# DS18B20.net
KiCad netlist of a schematic drawn in Altium Designer
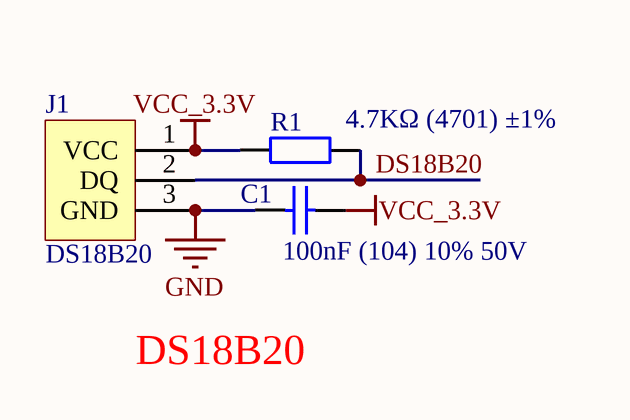
[diagram p0: DS18B20.SchDoc]

(export (version "E")
  (design (tool "Eeschema 10.0.6"))
  (components
    (comp (ref "C1")
      (value "100nF (104) 10% 50V")
      (footprint "CAPC_0603_2")
      (description "贴片电容")
      (libsource (lib "Cap") (part "0603 100nF (104) 10% 50V"))
    )
    (comp (ref "J1")
      (value "DS18B20")
      (footprint "XH_2.54_3P")
      (libsource (lib "工程-物联网温度实时监测设备") (part "Component_1_3"))
    )
    (comp (ref "R1")
      (value "4.7KΩ (4701) ±1%")
      (footprint "RESC_0603_2")
      (description "贴片电阻")
      (libsource (lib "RES") (part "0603 4.7KΩ (4701) 1%"))
    )
  )
  (nets
    (net (code "1") (name "/DS18B20") (class "Default")
      (node (ref "J1") (pin "2") (pinfunction "DQ_2") (pintype "passive"))
      (node (ref "R1") (pin "2") (pinfunction "2_2") (pintype "passive"))
    )
    (net (code "2") (name "GND") (class "Default")
      (node (ref "C1") (pin "1") (pinfunction "1_1") (pintype "passive"))
      (node (ref "J1") (pin "3") (pinfunction "GND_3") (pintype "passive"))
    )
    (net (code "3") (name "VCC_3.3V") (class "Default")
      (node (ref "C1") (pin "2") (pinfunction "2_2") (pintype "passive"))
      (node (ref "J1") (pin "1") (pinfunction "VCC_1") (pintype "passive"))
      (node (ref "R1") (pin "1") (pinfunction "1_1") (pintype "passive"))
    )
  )
)
